# STM32F042_EVAL.net
KiCad netlist of a schematic drawn in EAGLE
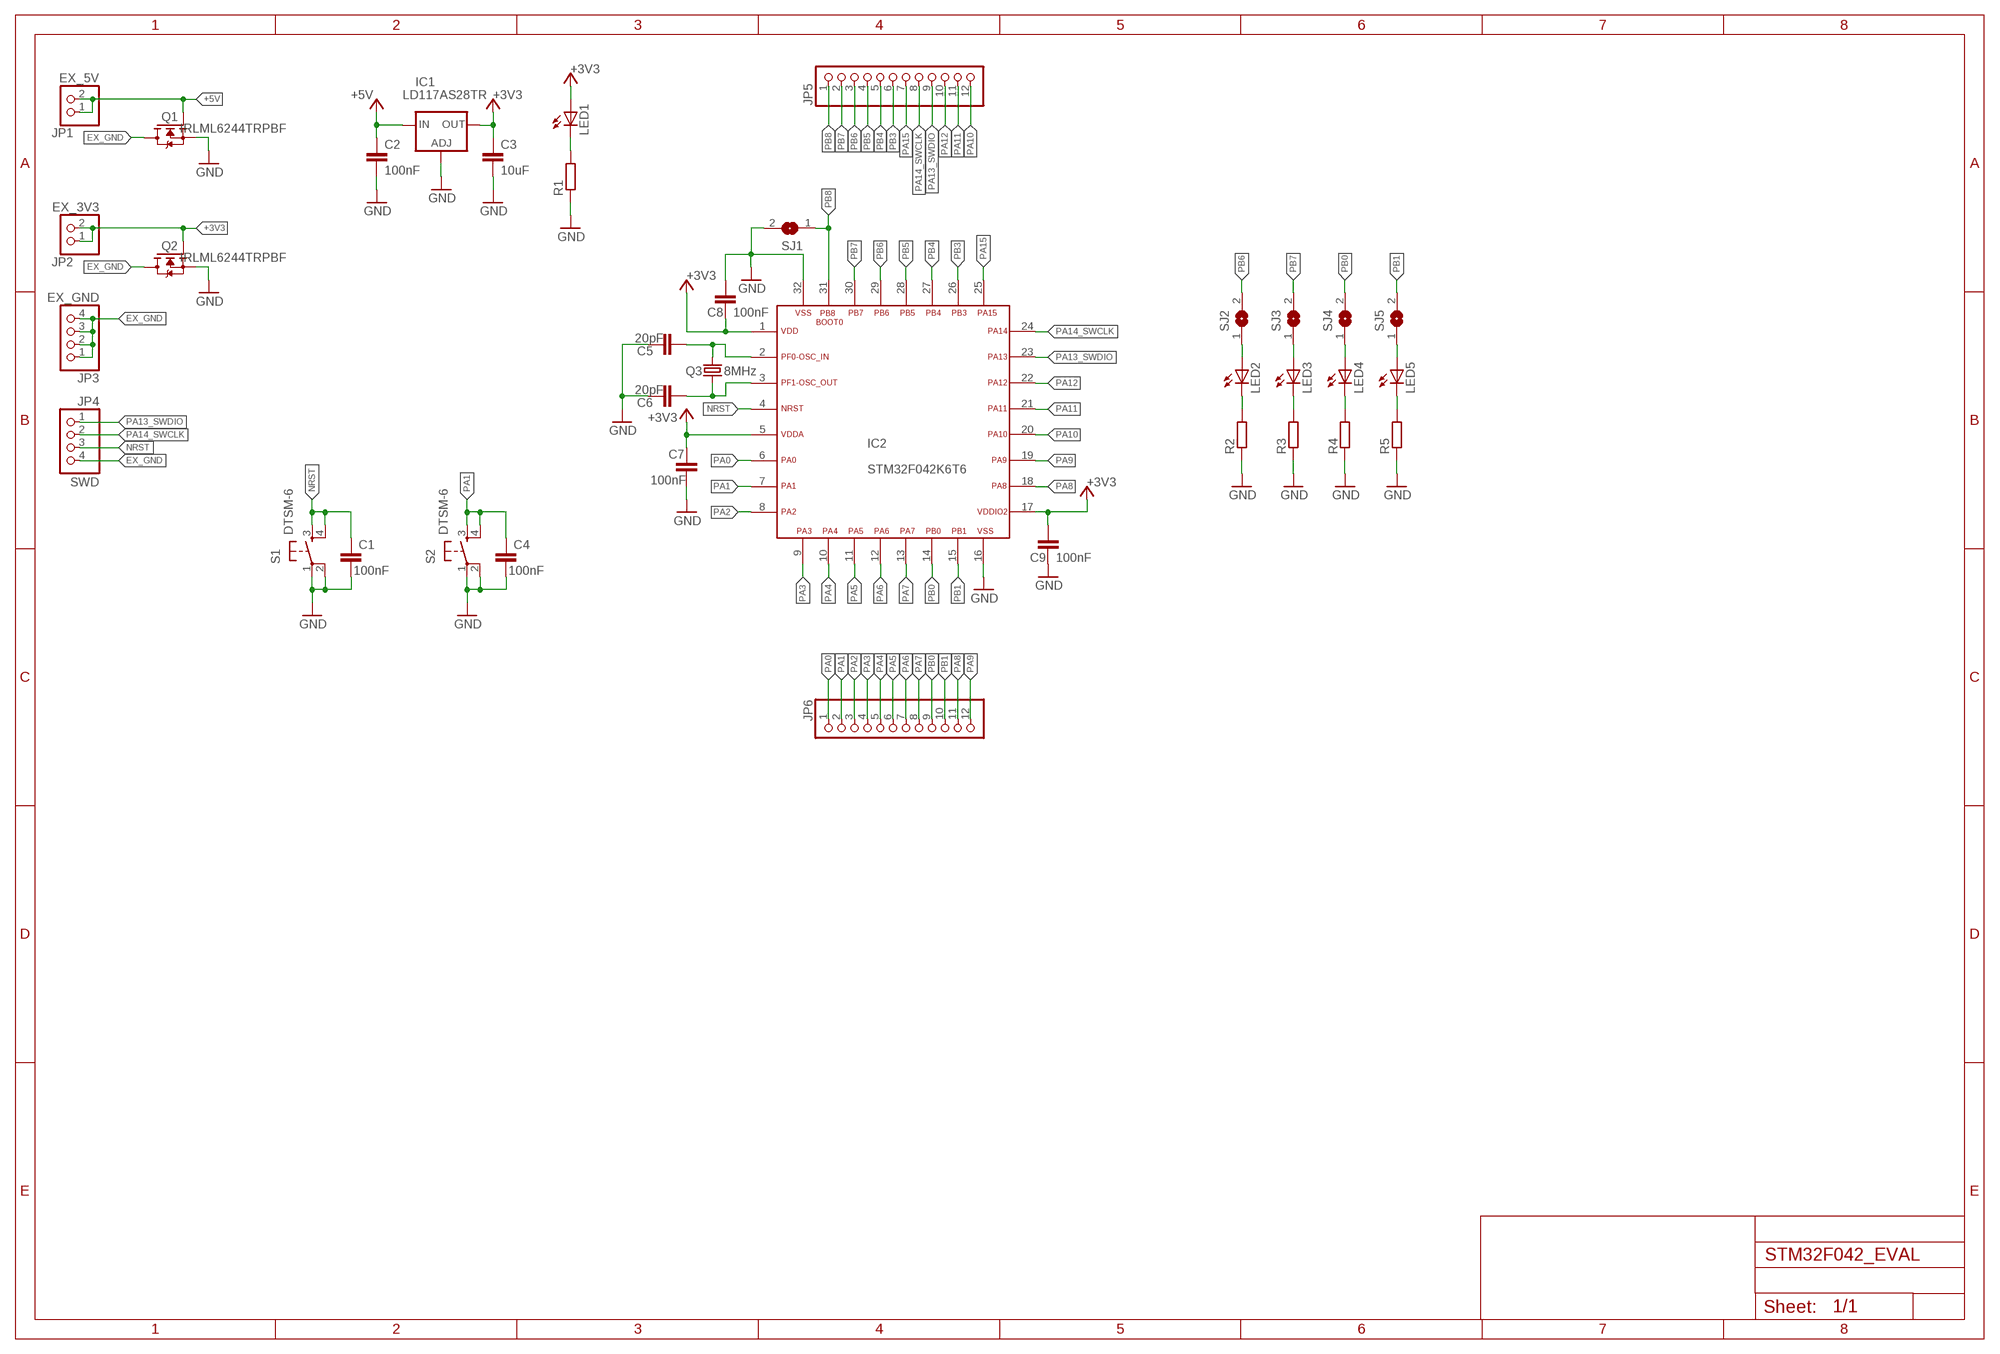
[diagram p0: schematic, sheet 1]

(export (version "E")
  (design (tool "Eeschema 10.0.6"))
  (components
    (comp (ref "C1")
      (value "100nF")
      (footprint "eagle-import:C0603")
      (libsource (lib "eagle-import") (part "C-EUC0603"))
    )
    (comp (ref "C2")
      (value "100nF")
      (footprint "eagle-import:C0603")
      (libsource (lib "eagle-import") (part "C-EUC0603"))
    )
    (comp (ref "C3")
      (value "10uF")
      (footprint "eagle-import:C0603")
      (libsource (lib "eagle-import") (part "C-EUC0603"))
    )
    (comp (ref "C4")
      (value "100nF")
      (footprint "eagle-import:C0603")
      (libsource (lib "eagle-import") (part "C-EUC0603"))
    )
    (comp (ref "C5")
      (value "20pF")
      (footprint "eagle-import:C0603")
      (libsource (lib "eagle-import") (part "C-EUC0603"))
    )
    (comp (ref "C6")
      (value "20pF")
      (footprint "eagle-import:C0603")
      (libsource (lib "eagle-import") (part "C-EUC0603"))
    )
    (comp (ref "C7")
      (value "100nF")
      (footprint "eagle-import:C0603")
      (libsource (lib "eagle-import") (part "C-EUC0603"))
    )
    (comp (ref "C8")
      (value "100nF")
      (footprint "eagle-import:C0603")
      (libsource (lib "eagle-import") (part "C-EUC0603"))
    )
    (comp (ref "C9")
      (value "100nF")
      (footprint "eagle-import:C0603")
      (libsource (lib "eagle-import") (part "C-EUC0603"))
    )
    (comp (ref "IC1")
      (value "LD117AS28TR")
      (footprint "eagle-import:SOT223")
      (libsource (lib "eagle-import") (part "LD117A?S28TR"))
    )
    (comp (ref "IC2")
      (value "STM32F042K6T6")
      (footprint "eagle-import:LQFP32-7X7")
      (libsource (lib "eagle-import") (part "STM32F042K6T6"))
    )
    (comp (ref "JP1")
      (value "EX_5V")
      (footprint "eagle-import:1X02")
      (libsource (lib "eagle-import") (part "PINHD-1X2"))
    )
    (comp (ref "JP2")
      (value "EX_3V3")
      (footprint "eagle-import:1X02")
      (libsource (lib "eagle-import") (part "PINHD-1X2"))
    )
    (comp (ref "JP3")
      (value "EX_GND")
      (footprint "eagle-import:1X04")
      (libsource (lib "eagle-import") (part "PINHD-1X4"))
    )
    (comp (ref "JP4")
      (value "SWD")
      (footprint "eagle-import:1X04")
      (libsource (lib "eagle-import") (part "PINHD-1X4"))
    )
    (comp (ref "JP5")
      (value "PINHD-1X12")
      (footprint "eagle-import:1X12")
      (libsource (lib "eagle-import") (part "PINHD-1X12"))
    )
    (comp (ref "JP6")
      (value "PINHD-1X12")
      (footprint "eagle-import:1X12")
      (libsource (lib "eagle-import") (part "PINHD-1X12"))
    )
    (comp (ref "LED1")
      (value "LEDCHIP-LED0603")
      (footprint "eagle-import:CHIP-LED0603")
      (libsource (lib "eagle-import") (part "LEDCHIP-LED0603"))
    )
    (comp (ref "LED2")
      (value "LEDCHIP-LED0603")
      (footprint "eagle-import:CHIP-LED0603")
      (libsource (lib "eagle-import") (part "LEDCHIP-LED0603"))
    )
    (comp (ref "LED3")
      (value "LEDCHIP-LED0603")
      (footprint "eagle-import:CHIP-LED0603")
      (libsource (lib "eagle-import") (part "LEDCHIP-LED0603"))
    )
    (comp (ref "LED4")
      (value "LEDCHIP-LED0603")
      (footprint "eagle-import:CHIP-LED0603")
      (libsource (lib "eagle-import") (part "LEDCHIP-LED0603"))
    )
    (comp (ref "LED5")
      (value "LEDCHIP-LED0603")
      (footprint "eagle-import:CHIP-LED0603")
      (libsource (lib "eagle-import") (part "LEDCHIP-LED0603"))
    )
    (comp (ref "Q1")
      (value "IRLML6244TRPBF")
      (footprint "eagle-import:SOT23")
      (libsource (lib "eagle-import") (part "IRLML6244TRPBF"))
    )
    (comp (ref "Q2")
      (value "IRLML6244TRPBF")
      (footprint "eagle-import:SOT23")
      (libsource (lib "eagle-import") (part "IRLML6244TRPBF"))
    )
    (comp (ref "Q3")
      (value "8MHz")
      (footprint "eagle-import:HC49UP")
      (libsource (lib "eagle-import") (part "CRYSTALHC49UP"))
    )
    (comp (ref "R1")
      (value "R-EU_R0603")
      (footprint "eagle-import:R0603")
      (libsource (lib "eagle-import") (part "R-EU_R0603"))
    )
    (comp (ref "R2")
      (value "R-EU_R0805")
      (footprint "eagle-import:R0805")
      (libsource (lib "eagle-import") (part "R-EU_R0805"))
    )
    (comp (ref "R3")
      (value "R-EU_R0805")
      (footprint "eagle-import:R0805")
      (libsource (lib "eagle-import") (part "R-EU_R0805"))
    )
    (comp (ref "R4")
      (value "R-EU_R0805")
      (footprint "eagle-import:R0805")
      (libsource (lib "eagle-import") (part "R-EU_R0805"))
    )
    (comp (ref "R5")
      (value "R-EU_R0805")
      (footprint "eagle-import:R0805")
      (libsource (lib "eagle-import") (part "R-EU_R0805"))
    )
    (comp (ref "S1")
      (value "DTSM-6")
      (footprint "eagle-import:DTSM-6")
      (libsource (lib "eagle-import") (part "DTSM-6"))
    )
    (comp (ref "S2")
      (value "DTSM-6")
      (footprint "eagle-import:DTSM-6")
      (libsource (lib "eagle-import") (part "DTSM-6"))
    )
    (comp (ref "SJ1") (value "SJ") (footprint "eagle-import:SJ") (libsource (lib "eagle-import") (part "SJ")))
    (comp (ref "SJ2") (value "SJ") (footprint "eagle-import:SJ") (libsource (lib "eagle-import") (part "SJ")))
    (comp (ref "SJ3") (value "SJ") (footprint "eagle-import:SJ") (libsource (lib "eagle-import") (part "SJ")))
    (comp (ref "SJ4") (value "SJ") (footprint "eagle-import:SJ") (libsource (lib "eagle-import") (part "SJ")))
    (comp (ref "SJ5") (value "SJ") (footprint "eagle-import:SJ") (libsource (lib "eagle-import") (part "SJ")))
  )
  (nets
    (net (code "1") (name "+3V3") (class "Default")
      (node (ref "C3") (pin "1") (pinfunction "1_1") (pintype "passive"))
      (node (ref "C7") (pin "1") (pinfunction "1_1") (pintype "passive"))
      (node (ref "C8") (pin "2") (pinfunction "2_2") (pintype "passive"))
      (node (ref "C9") (pin "1") (pinfunction "1_1") (pintype "passive"))
      (node (ref "IC1") (pin "4") (pinfunction "OUT_4") (pintype "passive"))
      (node (ref "IC2") (pin "1") (pinfunction "VDD_1") (pintype "power_in"))
      (node (ref "IC2") (pin "17") (pinfunction "VDDIO2_17") (pintype "power_in"))
      (node (ref "IC2") (pin "5") (pinfunction "VDDA_5") (pintype "power_in"))
      (node (ref "JP2") (pin "1") (pinfunction "1_1") (pintype "passive"))
      (node (ref "JP2") (pin "2") (pinfunction "2_2") (pintype "passive"))
      (node (ref "LED1") (pin "A") (pinfunction "A_A") (pintype "passive"))
      (node (ref "Q2") (pin "1") (pinfunction "G_1") (pintype "passive"))
    )
    (net (code "2") (name "+5V") (class "Default")
      (node (ref "C2") (pin "1") (pinfunction "1_1") (pintype "passive"))
      (node (ref "IC1") (pin "3") (pinfunction "IN_3") (pintype "input"))
      (node (ref "JP1") (pin "1") (pinfunction "1_1") (pintype "passive"))
      (node (ref "JP1") (pin "2") (pinfunction "2_2") (pintype "passive"))
      (node (ref "Q1") (pin "1") (pinfunction "G_1") (pintype "passive"))
    )
    (net (code "3") (name "EX_GND") (class "Default")
      (node (ref "JP3") (pin "1") (pinfunction "1_1") (pintype "passive"))
      (node (ref "JP3") (pin "2") (pinfunction "2_2") (pintype "passive"))
      (node (ref "JP3") (pin "3") (pinfunction "3_3") (pintype "passive"))
      (node (ref "JP3") (pin "4") (pinfunction "4_4") (pintype "passive"))
      (node (ref "JP4") (pin "4") (pinfunction "4_4") (pintype "passive"))
      (node (ref "Q1") (pin "3") (pinfunction "D_3") (pintype "passive"))
      (node (ref "Q2") (pin "3") (pinfunction "D_3") (pintype "passive"))
    )
    (net (code "4") (name "GND") (class "Default")
      (node (ref "C1") (pin "2") (pinfunction "2_2") (pintype "passive"))
      (node (ref "C2") (pin "2") (pinfunction "2_2") (pintype "passive"))
      (node (ref "C3") (pin "2") (pinfunction "2_2") (pintype "passive"))
      (node (ref "C4") (pin "2") (pinfunction "2_2") (pintype "passive"))
      (node (ref "C5") (pin "1") (pinfunction "1_1") (pintype "passive"))
      (node (ref "C6") (pin "1") (pinfunction "1_1") (pintype "passive"))
      (node (ref "C7") (pin "2") (pinfunction "2_2") (pintype "passive"))
      (node (ref "C8") (pin "1") (pinfunction "1_1") (pintype "passive"))
      (node (ref "C9") (pin "2") (pinfunction "2_2") (pintype "passive"))
      (node (ref "IC1") (pin "1") (pinfunction "ADJ_1") (pintype "input"))
      (node (ref "IC2") (pin "16") (pinfunction "VSS1_16") (pintype "power_in"))
      (node (ref "IC2") (pin "32") (pinfunction "VSS2_32") (pintype "power_in"))
      (node (ref "Q1") (pin "2") (pinfunction "S_2") (pintype "passive"))
      (node (ref "Q2") (pin "2") (pinfunction "S_2") (pintype "passive"))
      (node (ref "R1") (pin "1") (pinfunction "1_1") (pintype "passive"))
      (node (ref "R2") (pin "1") (pinfunction "1_1") (pintype "passive"))
      (node (ref "R3") (pin "1") (pinfunction "1_1") (pintype "passive"))
      (node (ref "R4") (pin "1") (pinfunction "1_1") (pintype "passive"))
      (node (ref "R5") (pin "1") (pinfunction "1_1") (pintype "passive"))
      (node (ref "S1") (pin "1") (pinfunction "1_1") (pintype "passive"))
      (node (ref "S1") (pin "2") (pinfunction "2_2") (pintype "passive"))
      (node (ref "S2") (pin "1") (pinfunction "1_1") (pintype "passive"))
      (node (ref "S2") (pin "2") (pinfunction "2_2") (pintype "passive"))
      (node (ref "SJ1") (pin "2") (pinfunction "2_2") (pintype "passive"))
    )
    (net (code "5") (name "NRST") (class "Default")
      (node (ref "C1") (pin "1") (pinfunction "1_1") (pintype "passive"))
      (node (ref "IC2") (pin "4") (pinfunction "NRST_4") (pintype "bidirectional"))
      (node (ref "JP4") (pin "3") (pinfunction "3_3") (pintype "passive"))
      (node (ref "S1") (pin "3") (pinfunction "3_3") (pintype "passive"))
      (node (ref "S1") (pin "4") (pinfunction "4_4") (pintype "passive"))
    )
    (net (code "6") (name "Net-(IC2-PF0-OSC_IN)") (class "Default")
      (node (ref "C5") (pin "2") (pinfunction "2_2") (pintype "passive"))
      (node (ref "IC2") (pin "2") (pinfunction "PF0-OSC_IN_2") (pintype "bidirectional"))
      (node (ref "Q3") (pin "2") (pinfunction "2_2") (pintype "passive"))
    )
    (net (code "7") (name "Net-(IC2-PF1-OSC_OUT)") (class "Default")
      (node (ref "C6") (pin "2") (pinfunction "2_2") (pintype "passive"))
      (node (ref "IC2") (pin "3") (pinfunction "PF1-OSC_OUT_3") (pintype "bidirectional"))
      (node (ref "Q3") (pin "1") (pinfunction "1_1") (pintype "passive"))
    )
    (net (code "8") (name "Net-(LED1-PadC)") (class "Default")
      (node (ref "LED1") (pin "C") (pinfunction "C_C") (pintype "passive"))
      (node (ref "R1") (pin "2") (pinfunction "2_2") (pintype "passive"))
    )
    (net (code "9") (name "Net-(LED2-PadA)") (class "Default")
      (node (ref "LED2") (pin "A") (pinfunction "A_A") (pintype "passive"))
      (node (ref "SJ2") (pin "1") (pinfunction "1_1") (pintype "passive"))
    )
    (net (code "10") (name "Net-(LED2-PadC)") (class "Default")
      (node (ref "LED2") (pin "C") (pinfunction "C_C") (pintype "passive"))
      (node (ref "R2") (pin "2") (pinfunction "2_2") (pintype "passive"))
    )
    (net (code "11") (name "Net-(LED3-PadA)") (class "Default")
      (node (ref "LED3") (pin "A") (pinfunction "A_A") (pintype "passive"))
      (node (ref "SJ3") (pin "1") (pinfunction "1_1") (pintype "passive"))
    )
    (net (code "12") (name "Net-(LED3-PadC)") (class "Default")
      (node (ref "LED3") (pin "C") (pinfunction "C_C") (pintype "passive"))
      (node (ref "R3") (pin "2") (pinfunction "2_2") (pintype "passive"))
    )
    (net (code "13") (name "Net-(LED4-PadA)") (class "Default")
      (node (ref "LED4") (pin "A") (pinfunction "A_A") (pintype "passive"))
      (node (ref "SJ4") (pin "1") (pinfunction "1_1") (pintype "passive"))
    )
    (net (code "14") (name "Net-(LED4-PadC)") (class "Default")
      (node (ref "LED4") (pin "C") (pinfunction "C_C") (pintype "passive"))
      (node (ref "R4") (pin "2") (pinfunction "2_2") (pintype "passive"))
    )
    (net (code "15") (name "Net-(LED5-PadA)") (class "Default")
      (node (ref "LED5") (pin "A") (pinfunction "A_A") (pintype "passive"))
      (node (ref "SJ5") (pin "1") (pinfunction "1_1") (pintype "passive"))
    )
    (net (code "16") (name "Net-(LED5-PadC)") (class "Default")
      (node (ref "LED5") (pin "C") (pinfunction "C_C") (pintype "passive"))
      (node (ref "R5") (pin "2") (pinfunction "2_2") (pintype "passive"))
    )
    (net (code "17") (name "PA0") (class "Default")
      (node (ref "IC2") (pin "6") (pinfunction "PA0_6") (pintype "bidirectional"))
      (node (ref "JP6") (pin "1") (pinfunction "1_1") (pintype "passive"))
    )
    (net (code "18") (name "PA1") (class "Default")
      (node (ref "C4") (pin "1") (pinfunction "1_1") (pintype "passive"))
      (node (ref "IC2") (pin "7") (pinfunction "PA1_7") (pintype "bidirectional"))
      (node (ref "JP6") (pin "2") (pinfunction "2_2") (pintype "passive"))
      (node (ref "S2") (pin "3") (pinfunction "3_3") (pintype "passive"))
      (node (ref "S2") (pin "4") (pinfunction "4_4") (pintype "passive"))
    )
    (net (code "19") (name "PA2") (class "Default")
      (node (ref "IC2") (pin "8") (pinfunction "PA2_8") (pintype "bidirectional"))
      (node (ref "JP6") (pin "3") (pinfunction "3_3") (pintype "passive"))
    )
    (net (code "20") (name "PA3") (class "Default")
      (node (ref "IC2") (pin "9") (pinfunction "PA3_9") (pintype "bidirectional"))
      (node (ref "JP6") (pin "4") (pinfunction "4_4") (pintype "passive"))
    )
    (net (code "21") (name "PA4") (class "Default")
      (node (ref "IC2") (pin "10") (pinfunction "PA4_10") (pintype "bidirectional"))
      (node (ref "JP6") (pin "5") (pinfunction "5_5") (pintype "passive"))
    )
    (net (code "22") (name "PA5") (class "Default")
      (node (ref "IC2") (pin "11") (pinfunction "PA5_11") (pintype "bidirectional"))
      (node (ref "JP6") (pin "6") (pinfunction "6_6") (pintype "passive"))
    )
    (net (code "23") (name "PA6") (class "Default")
      (node (ref "IC2") (pin "12") (pinfunction "PA6_12") (pintype "bidirectional"))
      (node (ref "JP6") (pin "7") (pinfunction "7_7") (pintype "passive"))
    )
    (net (code "24") (name "PA7") (class "Default")
      (node (ref "IC2") (pin "13") (pinfunction "PA7_13") (pintype "bidirectional"))
      (node (ref "JP6") (pin "8") (pinfunction "8_8") (pintype "passive"))
    )
    (net (code "25") (name "PA8") (class "Default")
      (node (ref "IC2") (pin "18") (pinfunction "PA8_18") (pintype "bidirectional"))
      (node (ref "JP6") (pin "11") (pinfunction "11_11") (pintype "passive"))
    )
    (net (code "26") (name "PA9") (class "Default")
      (node (ref "IC2") (pin "19") (pinfunction "PA9_19") (pintype "bidirectional"))
      (node (ref "JP6") (pin "12") (pinfunction "12_12") (pintype "passive"))
    )
    (net (code "27") (name "PA10") (class "Default")
      (node (ref "IC2") (pin "20") (pinfunction "PA10_20") (pintype "bidirectional"))
      (node (ref "JP5") (pin "12") (pinfunction "12_12") (pintype "passive"))
    )
    (net (code "28") (name "PA11") (class "Default")
      (node (ref "IC2") (pin "21") (pinfunction "PA11_21") (pintype "bidirectional"))
      (node (ref "JP5") (pin "11") (pinfunction "11_11") (pintype "passive"))
    )
    (net (code "29") (name "PA12") (class "Default")
      (node (ref "IC2") (pin "22") (pinfunction "PA12_22") (pintype "bidirectional"))
      (node (ref "JP5") (pin "10") (pinfunction "10_10") (pintype "passive"))
    )
    (net (code "30") (name "PA13_SWDIO") (class "Default")
      (node (ref "IC2") (pin "23") (pinfunction "PA13_23") (pintype "bidirectional"))
      (node (ref "JP4") (pin "1") (pinfunction "1_1") (pintype "passive"))
      (node (ref "JP5") (pin "9") (pinfunction "9_9") (pintype "passive"))
    )
    (net (code "31") (name "PA14_SWCLK") (class "Default")
      (node (ref "IC2") (pin "24") (pinfunction "PA14_24") (pintype "bidirectional"))
      (node (ref "JP4") (pin "2") (pinfunction "2_2") (pintype "passive"))
      (node (ref "JP5") (pin "8") (pinfunction "8_8") (pintype "passive"))
    )
    (net (code "32") (name "PA15") (class "Default")
      (node (ref "IC2") (pin "25") (pinfunction "PA15_25") (pintype "bidirectional"))
      (node (ref "JP5") (pin "7") (pinfunction "7_7") (pintype "passive"))
    )
    (net (code "33") (name "PB0") (class "Default")
      (node (ref "IC2") (pin "14") (pinfunction "PB0_14") (pintype "bidirectional"))
      (node (ref "JP6") (pin "9") (pinfunction "9_9") (pintype "passive"))
      (node (ref "SJ4") (pin "2") (pinfunction "2_2") (pintype "passive"))
    )
    (net (code "34") (name "PB1") (class "Default")
      (node (ref "IC2") (pin "15") (pinfunction "PB1_15") (pintype "bidirectional"))
      (node (ref "JP6") (pin "10") (pinfunction "10_10") (pintype "passive"))
      (node (ref "SJ5") (pin "2") (pinfunction "2_2") (pintype "passive"))
    )
    (net (code "35") (name "PB3") (class "Default")
      (node (ref "IC2") (pin "26") (pinfunction "PB3_26") (pintype "bidirectional"))
      (node (ref "JP5") (pin "6") (pinfunction "6_6") (pintype "passive"))
    )
    (net (code "36") (name "PB4") (class "Default")
      (node (ref "IC2") (pin "27") (pinfunction "PB4_27") (pintype "bidirectional"))
      (node (ref "JP5") (pin "5") (pinfunction "5_5") (pintype "passive"))
    )
    (net (code "37") (name "PB5") (class "Default")
      (node (ref "IC2") (pin "28") (pinfunction "PB5_28") (pintype "bidirectional"))
      (node (ref "JP5") (pin "4") (pinfunction "4_4") (pintype "passive"))
    )
    (net (code "38") (name "PB6") (class "Default")
      (node (ref "IC2") (pin "29") (pinfunction "PB6_29") (pintype "bidirectional"))
      (node (ref "JP5") (pin "3") (pinfunction "3_3") (pintype "passive"))
      (node (ref "SJ2") (pin "2") (pinfunction "2_2") (pintype "passive"))
    )
    (net (code "39") (name "PB7") (class "Default")
      (node (ref "IC2") (pin "30") (pinfunction "PB7_30") (pintype "bidirectional"))
      (node (ref "JP5") (pin "2") (pinfunction "2_2") (pintype "passive"))
      (node (ref "SJ3") (pin "2") (pinfunction "2_2") (pintype "passive"))
    )
    (net (code "40") (name "PB8") (class "Default")
      (node (ref "IC2") (pin "31") (pinfunction "PB8-BOOT0_31") (pintype "bidirectional"))
      (node (ref "JP5") (pin "1") (pinfunction "1_1") (pintype "passive"))
      (node (ref "SJ1") (pin "1") (pinfunction "1_1") (pintype "passive"))
    )
  )
)
